# Linear_Amplifier_Interface.net
KiCad netlist of a schematic drawn in EAGLE
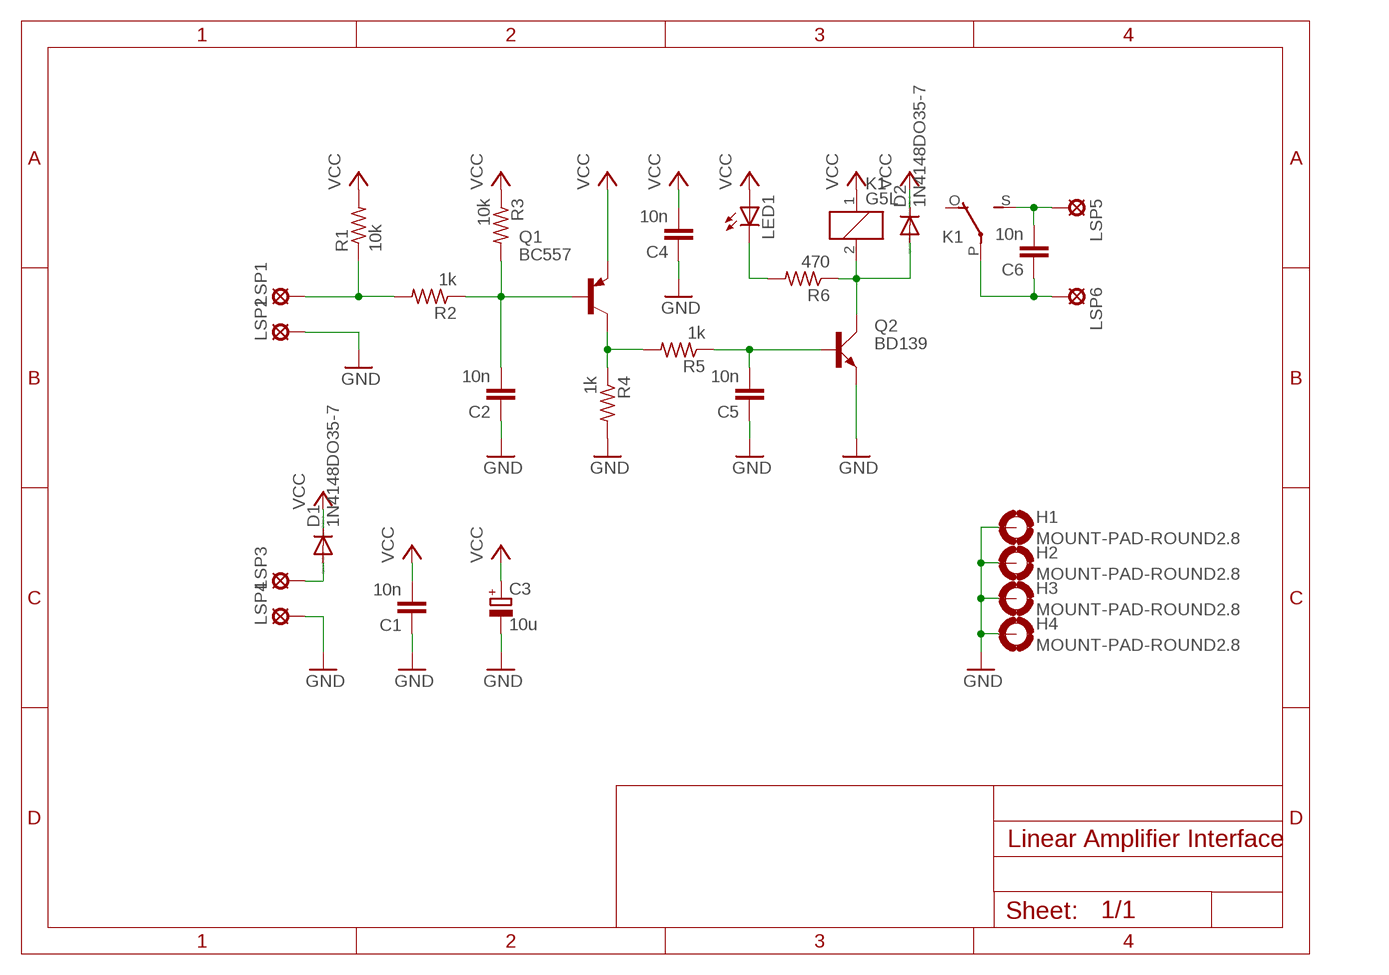
[diagram p0: schematic, sheet 1]

(export (version "E")
  (design (tool "Eeschema 10.0.6"))
  (components
    (comp (ref "C1")
      (value "10n")
      (footprint "eagle-import:C1206K")
      (libsource (lib "eagle-import") (part "C-EUC1206K"))
    )
    (comp (ref "C2")
      (value "10n")
      (footprint "eagle-import:C1206K")
      (libsource (lib "eagle-import") (part "C-EUC1206K"))
    )
    (comp (ref "C3")
      (value "10u")
      (footprint "eagle-import:E5-6")
      (libsource (lib "eagle-import") (part "CPOL-EUE5-6"))
    )
    (comp (ref "C4")
      (value "10n")
      (footprint "eagle-import:C1206K")
      (libsource (lib "eagle-import") (part "C-EUC1206K"))
    )
    (comp (ref "C5")
      (value "10n")
      (footprint "eagle-import:C1206K")
      (libsource (lib "eagle-import") (part "C-EUC1206K"))
    )
    (comp (ref "C6")
      (value "10n")
      (footprint "eagle-import:C1206K")
      (libsource (lib "eagle-import") (part "C-EUC1206K"))
    )
    (comp (ref "D1")
      (value "1N4148DO35-7")
      (footprint "eagle-import:DO35-7")
      (libsource (lib "eagle-import") (part "1N4148DO35-7"))
    )
    (comp (ref "D2")
      (value "1N4148DO35-7")
      (footprint "eagle-import:DO35-7")
      (libsource (lib "eagle-import") (part "1N4148DO35-7"))
    )
    (comp (ref "H1")
      (value "MOUNT-PAD-ROUND2.8")
      (footprint "eagle-import:2,8-PAD")
      (libsource (lib "eagle-import") (part "MOUNT-PAD-ROUND2.8"))
    )
    (comp (ref "H2")
      (value "MOUNT-PAD-ROUND2.8")
      (footprint "eagle-import:2,8-PAD")
      (libsource (lib "eagle-import") (part "MOUNT-PAD-ROUND2.8"))
    )
    (comp (ref "H3")
      (value "MOUNT-PAD-ROUND2.8")
      (footprint "eagle-import:2,8-PAD")
      (libsource (lib "eagle-import") (part "MOUNT-PAD-ROUND2.8"))
    )
    (comp (ref "H4")
      (value "MOUNT-PAD-ROUND2.8")
      (footprint "eagle-import:2,8-PAD")
      (libsource (lib "eagle-import") (part "MOUNT-PAD-ROUND2.8"))
    )
    (comp (ref "K1")
      (value "G5L")
      (footprint "eagle-import:G5LE")
      (libsource (lib "eagle-import") (part "G5L"))
    )
    (comp (ref "LED1")
      (value "LED3MM")
      (footprint "eagle-import:LED3MM")
      (libsource (lib "eagle-import") (part "LED3MM"))
    )
    (comp (ref "LSP1")
      (value "SE11")
      (footprint "eagle-import:SE11")
      (libsource (lib "eagle-import") (part "SE11"))
    )
    (comp (ref "LSP2")
      (value "SE11")
      (footprint "eagle-import:SE11")
      (libsource (lib "eagle-import") (part "SE11"))
    )
    (comp (ref "LSP3")
      (value "SE11")
      (footprint "eagle-import:SE11")
      (libsource (lib "eagle-import") (part "SE11"))
    )
    (comp (ref "LSP4")
      (value "SE11")
      (footprint "eagle-import:SE11")
      (libsource (lib "eagle-import") (part "SE11"))
    )
    (comp (ref "LSP5")
      (value "SE11")
      (footprint "eagle-import:SE11")
      (libsource (lib "eagle-import") (part "SE11"))
    )
    (comp (ref "LSP6")
      (value "SE11")
      (footprint "eagle-import:SE11")
      (libsource (lib "eagle-import") (part "SE11"))
    )
    (comp (ref "Q1")
      (value "BC557")
      (footprint "eagle-import:TO92-EBC")
      (libsource (lib "eagle-import") (part "BC557"))
    )
    (comp (ref "Q2")
      (value "BD139")
      (footprint "eagle-import:TO126AV")
      (libsource (lib "eagle-import") (part "BD139"))
    )
    (comp (ref "R1")
      (value "10k")
      (footprint "eagle-import:M1206")
      (libsource (lib "eagle-import") (part "R-US_M1206"))
    )
    (comp (ref "R2")
      (value "1k")
      (footprint "eagle-import:M1206")
      (libsource (lib "eagle-import") (part "R-US_M1206"))
    )
    (comp (ref "R3")
      (value "10k")
      (footprint "eagle-import:M1206")
      (libsource (lib "eagle-import") (part "R-US_M1206"))
    )
    (comp (ref "R4")
      (value "1k")
      (footprint "eagle-import:M1206")
      (libsource (lib "eagle-import") (part "R-US_M1206"))
    )
    (comp (ref "R5")
      (value "1k")
      (footprint "eagle-import:M1206")
      (libsource (lib "eagle-import") (part "R-US_M1206"))
    )
    (comp (ref "R6")
      (value "470")
      (footprint "eagle-import:M1206")
      (libsource (lib "eagle-import") (part "R-US_M1206"))
    )
  )
  (nets
    (net (code "1") (name "GND") (class "Default")
      (node (ref "C1") (pin "1") (pinfunction "1_1") (pintype "passive"))
      (node (ref "C2") (pin "1") (pinfunction "1_1") (pintype "passive"))
      (node (ref "C3") (pin "-") (pinfunction "-_-") (pintype "passive"))
      (node (ref "C4") (pin "1") (pinfunction "1_1") (pintype "passive"))
      (node (ref "C5") (pin "1") (pinfunction "1_1") (pintype "passive"))
      (node (ref "H1") (pin "B2,8") (pinfunction "MOUNT_B2,8") (pintype "passive"))
      (node (ref "H2") (pin "B2,8") (pinfunction "MOUNT_B2,8") (pintype "passive"))
      (node (ref "H3") (pin "B2,8") (pinfunction "MOUNT_B2,8") (pintype "passive"))
      (node (ref "H4") (pin "B2,8") (pinfunction "MOUNT_B2,8") (pintype "passive"))
      (node (ref "LSP2") (pin "MP") (pinfunction "MP_MP") (pintype "passive"))
      (node (ref "LSP4") (pin "MP") (pinfunction "MP_MP") (pintype "passive"))
      (node (ref "Q2") (pin "E") (pinfunction "E_E") (pintype "passive"))
      (node (ref "R4") (pin "2") (pinfunction "2_2") (pintype "passive"))
    )
    (net (code "2") (name "Net-(C2-Pad2)") (class "Default")
      (node (ref "C2") (pin "2") (pinfunction "2_2") (pintype "passive"))
      (node (ref "Q1") (pin "B") (pinfunction "B_B") (pintype "passive"))
      (node (ref "R2") (pin "1") (pinfunction "1_1") (pintype "passive"))
      (node (ref "R3") (pin "2") (pinfunction "2_2") (pintype "passive"))
    )
    (net (code "3") (name "Net-(C5-Pad2)") (class "Default")
      (node (ref "C5") (pin "2") (pinfunction "2_2") (pintype "passive"))
      (node (ref "Q2") (pin "B") (pinfunction "B_B") (pintype "passive"))
      (node (ref "R5") (pin "1") (pinfunction "1_1") (pintype "passive"))
    )
    (net (code "4") (name "Net-(C6-Pad1)") (class "Default")
      (node (ref "C6") (pin "1") (pinfunction "1_1") (pintype "passive"))
      (node (ref "K1") (pin "P") (pinfunction "P_P") (pintype "passive"))
      (node (ref "LSP6") (pin "MP") (pinfunction "MP_MP") (pintype "passive"))
    )
    (net (code "5") (name "Net-(C6-Pad2)") (class "Default")
      (node (ref "C6") (pin "2") (pinfunction "2_2") (pintype "passive"))
      (node (ref "K1") (pin "S") (pinfunction "S_S") (pintype "passive"))
      (node (ref "LSP5") (pin "MP") (pinfunction "MP_MP") (pintype "passive"))
    )
    (net (code "6") (name "Net-(D1-PadA)") (class "Default")
      (node (ref "D1") (pin "A") (pinfunction "A_A") (pintype "passive"))
      (node (ref "LSP3") (pin "MP") (pinfunction "MP_MP") (pintype "passive"))
    )
    (net (code "7") (name "Net-(D2-PadA)") (class "Default")
      (node (ref "D2") (pin "A") (pinfunction "A_A") (pintype "passive"))
      (node (ref "K1") (pin "2") (pinfunction "2_2") (pintype "passive"))
      (node (ref "Q2") (pin "C") (pinfunction "C_C") (pintype "passive"))
      (node (ref "R6") (pin "1") (pinfunction "1_1") (pintype "passive"))
    )
    (net (code "8") (name "Net-(LED1-C)") (class "Default")
      (node (ref "LED1") (pin "K") (pinfunction "C_K") (pintype "passive"))
      (node (ref "R6") (pin "2") (pinfunction "2_2") (pintype "passive"))
    )
    (net (code "9") (name "Net-(LSP1-PadMP)") (class "Default")
      (node (ref "LSP1") (pin "MP") (pinfunction "MP_MP") (pintype "passive"))
      (node (ref "R1") (pin "1") (pinfunction "1_1") (pintype "passive"))
      (node (ref "R2") (pin "2") (pinfunction "2_2") (pintype "passive"))
    )
    (net (code "10") (name "Net-(Q1-PadC)") (class "Default")
      (node (ref "Q1") (pin "C") (pinfunction "C_C") (pintype "passive"))
      (node (ref "R4") (pin "1") (pinfunction "1_1") (pintype "passive"))
      (node (ref "R5") (pin "2") (pinfunction "2_2") (pintype "passive"))
    )
    (net (code "11") (name "VCC") (class "Default")
      (node (ref "C1") (pin "2") (pinfunction "2_2") (pintype "passive"))
      (node (ref "C3") (pin "+") (pinfunction "+_+") (pintype "passive"))
      (node (ref "C4") (pin "2") (pinfunction "2_2") (pintype "passive"))
      (node (ref "D1") (pin "C") (pinfunction "C_C") (pintype "passive"))
      (node (ref "D2") (pin "C") (pinfunction "C_C") (pintype "passive"))
      (node (ref "K1") (pin "1") (pinfunction "1_1") (pintype "passive"))
      (node (ref "LED1") (pin "A") (pinfunction "A_A") (pintype "passive"))
      (node (ref "Q1") (pin "E") (pinfunction "E_E") (pintype "passive"))
      (node (ref "R1") (pin "2") (pinfunction "2_2") (pintype "passive"))
      (node (ref "R3") (pin "1") (pinfunction "1_1") (pintype "passive"))
    )
    (net (code "12") (name "unconnected-(K1-PadO)") (class "Default")
      (node (ref "K1") (pin "O") (pinfunction "O_O") (pintype "passive"))
    )
  )
)
